# NUC_power.net
KiCad netlist of a schematic drawn in Altium Designer
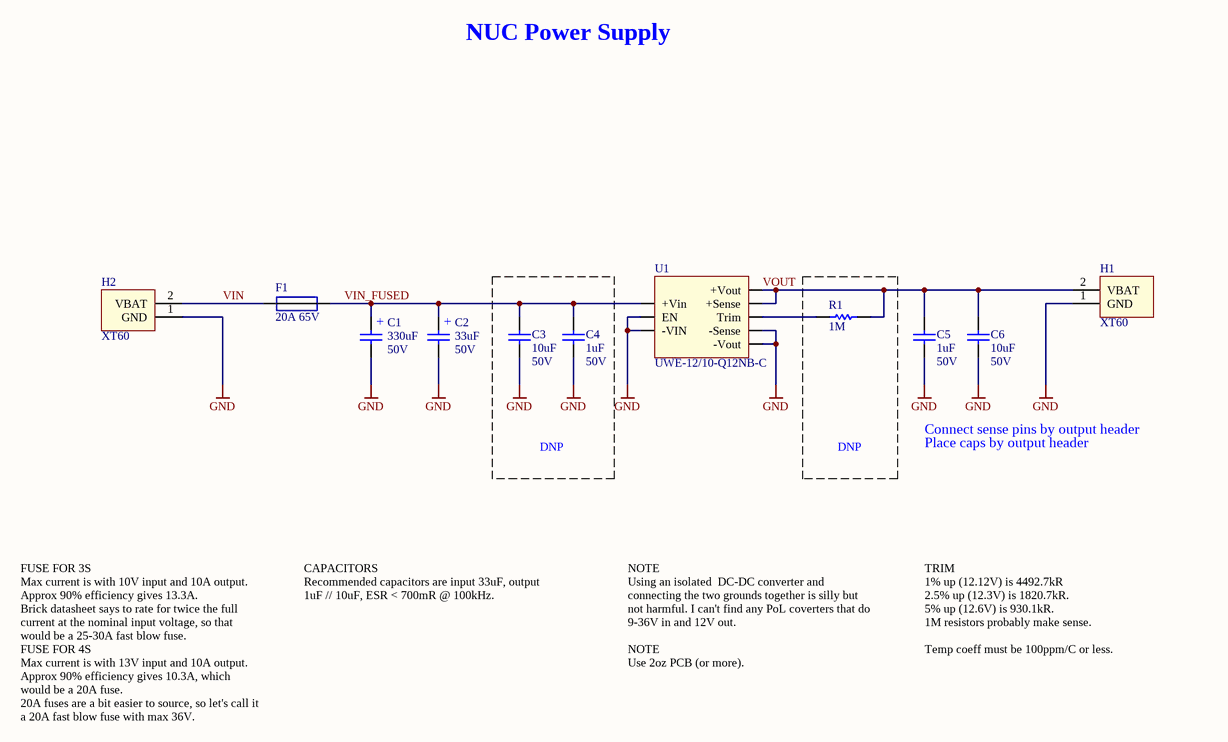
[diagram p0: NUC_power.SchDoc]

(export (version "E")
  (design (tool "Eeschema 10.0.6"))
  (components
    (comp (ref "C1")
      (value "330uF")
      (footprint "CAP_16x10")
      (description "Cap TH 330uF 50V")
      (fields (field (name "MAX VOLTAGE") "50V"))
      (libsource (lib "Passives") (part "CAP_TH_330U"))
    )
    (comp (ref "C2")
      (value "33uF")
      (footprint "CAP_11x5")
      (description "Cap TH 33uF 50V")
      (fields (field (name "MAX VOLTAGE") "50V"))
      (libsource (lib "Passives") (part "CAP_TH_33U"))
    )
    (comp (ref "C3")
      (value "10uF")
      (footprint "CAPC3225L")
      (description "CAP CER 10UF X7S +-10% 50V 1210")
      (fields
        (field (name "MANUFACTURER") "Murata")
        (field (name "MANUFACTURER PART NUMBER") "GCM32EC71H106KA03L")
        (field (name "MAX VOLTAGE") "50V")
      )
      (libsource (lib "Passives") (part "CC_10uF_1210"))
    )
    (comp (ref "C4")
      (value "1uF")
      (footprint "CAPC2012L")
      (description "CAP CER 1uF X7R +-10% 50V 0805")
      (fields
        (field (name "MANUFACTURER") "Samsung")
        (field (name "MANUFACTURER PART NUMBER") "CL21B105KBFNNNG")
        (field (name "MAX VOLTAGE") "50V")
      )
      (libsource (lib "Passives") (part "CC_1uF_0805"))
    )
    (comp (ref "C5")
      (value "1uF")
      (footprint "CAPC2012L")
      (description "CAP CER 1uF X7R +-10% 50V 0805")
      (fields
        (field (name "MANUFACTURER") "Samsung")
        (field (name "MANUFACTURER PART NUMBER") "CL21B105KBFNNNG")
        (field (name "MAX VOLTAGE") "50V")
      )
      (libsource (lib "Passives") (part "CC_1uF_0805"))
    )
    (comp (ref "C6")
      (value "10uF")
      (footprint "CAPC3225L")
      (description "CAP CER 10UF X7S +-10% 50V 1210")
      (fields
        (field (name "MANUFACTURER") "Murata")
        (field (name "MANUFACTURER PART NUMBER") "GCM32EC71H106KA03L")
        (field (name "MAX VOLTAGE") "50V")
      )
      (libsource (lib "Passives") (part "CC_10uF_1210"))
    )
    (comp (ref "F1")
      (value "20A 65V")
      (footprint "2410_FUSE")
      (description "FUSE FAST BLOW 20A 65V 2410")
      (libsource (lib "Passives") (part "FUSE_20A"))
    )
    (comp (ref "H1")
      (value "XT60")
      (footprint "XT60")
      (description "XT60 Connector Male/Female")
      (fields
        (field (name "MANUFACTURER_PART_NUMBER") "PRT-10474")
        (field (name "MOUSER PART NUMBER") "474-PRT-10474")
      )
      (libsource (lib "") (part "XT60_1"))
    )
    (comp (ref "H2")
      (value "XT60")
      (footprint "XT60")
      (description "XT60 Connector Male/Female")
      (fields
        (field (name "MANUFACTURER_PART_NUMBER") "PRT-10474")
        (field (name "MOUSER PART NUMBER") "474-PRT-10474")
      )
      (libsource (lib "Misc") (part "XT60"))
    )
    (comp (ref "R1")
      (value "1M")
      (footprint "RESC1608L")
      (description "RES 1.0M OHM 1/10W 5% 0603 SMD")
      (libsource (lib "Passives") (part "RS_1M"))
    )
    (comp (ref "U1")
      (value "UWE-12/10-Q12NB-C")
      (footprint "MURATA_UWE-100-120W with 1/16")
      (description "Isolated Module DC DC Converter 1 Output 12V 10A 9V - 36V Input")
      (fields (field (name "MANUFACTURER") "Murata Power Solutions Inc."))
      (libsource (lib "DOSA_bricks") (part "UWE-12/10-Q12NB-C"))
    )
  )
  (nets
    (net (code "1") (name "/VIN") (class "Default")
      (node (ref "F1") (pin "0") (pinfunction "0_0") (pintype "passive"))
      (node (ref "H2") (pin "2") (pinfunction "VBAT_2") (pintype "power_in"))
    )
    (net (code "2") (name "/VIN_FUSED") (class "Default")
      (node (ref "C1") (pin "1") (pinfunction "1_1") (pintype "passive"))
      (node (ref "C2") (pin "1") (pinfunction "1_1") (pintype "passive"))
      (node (ref "C3") (pin "2") (pinfunction "2_2") (pintype "passive"))
      (node (ref "C4") (pin "2") (pinfunction "2_2") (pintype "passive"))
      (node (ref "F1") (pin "1") (pinfunction "1_1") (pintype "passive"))
      (node (ref "U1") (pin "1") (pinfunction "+Vin_1") (pintype "power_in"))
    )
    (net (code "3") (name "/VOUT") (class "Default")
      (node (ref "C5") (pin "2") (pinfunction "2_2") (pintype "passive"))
      (node (ref "C6") (pin "2") (pinfunction "2_2") (pintype "passive"))
      (node (ref "H1") (pin "2") (pinfunction "VBAT_2") (pintype "power_in"))
      (node (ref "R1") (pin "2") (pinfunction "2_2") (pintype "passive"))
      (node (ref "U1") (pin "7") (pinfunction "+Sense_7") (pintype "passive"))
      (node (ref "U1") (pin "8") (pinfunction "+Vout_8") (pintype "power_in"))
    )
    (net (code "4") (name "GND") (class "Default")
      (node (ref "C1") (pin "2") (pinfunction "2_2") (pintype "passive"))
      (node (ref "C2") (pin "2") (pinfunction "2_2") (pintype "passive"))
      (node (ref "C3") (pin "1") (pinfunction "1_1") (pintype "passive"))
      (node (ref "C4") (pin "1") (pinfunction "1_1") (pintype "passive"))
      (node (ref "C5") (pin "1") (pinfunction "1_1") (pintype "passive"))
      (node (ref "C6") (pin "1") (pinfunction "1_1") (pintype "passive"))
      (node (ref "H1") (pin "1") (pinfunction "GND_1") (pintype "passive"))
      (node (ref "H2") (pin "1") (pinfunction "GND_1") (pintype "passive"))
      (node (ref "U1") (pin "2") (pinfunction "EN_2") (pintype "passive"))
      (node (ref "U1") (pin "3") (pinfunction "-VIN_3") (pintype "power_in"))
      (node (ref "U1") (pin "4") (pinfunction "-Vout_4") (pintype "power_in"))
      (node (ref "U1") (pin "5") (pinfunction "-Sense_5") (pintype "passive"))
    )
    (net (code "5") (name "Net-(U1-Trim)") (class "Default")
      (node (ref "R1") (pin "1") (pinfunction "1_1") (pintype "passive"))
      (node (ref "U1") (pin "6") (pinfunction "Trim_6") (pintype "passive"))
    )
  )
)
